# 03_POWER.net
KiCad netlist of a schematic drawn in Altium Designer
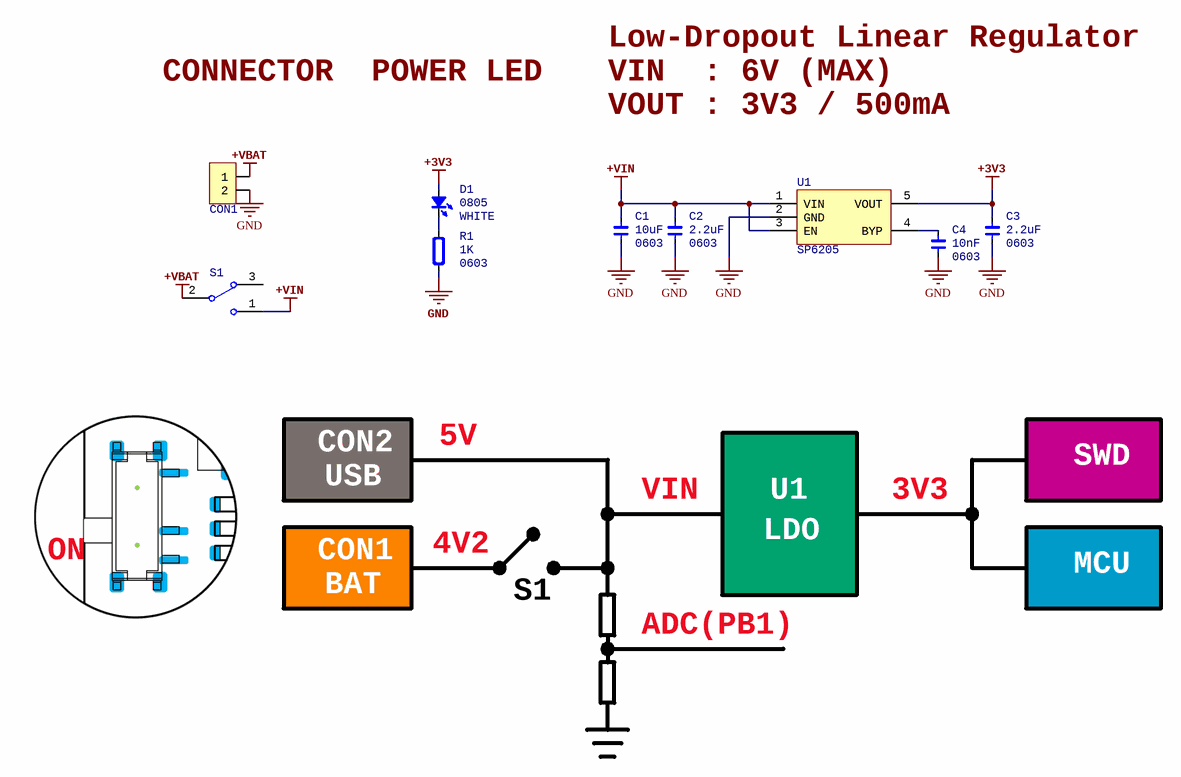
[diagram p0: [03] POWER.SchDoc]

(export (version "E")
  (design (tool "Eeschema 10.0.6"))
  (components
    (comp (ref "C1")
      (value "10uF")
      (footprint "PCB_PassiveCap:CAP_0603")
      (description "Capacitor")
      (fields (field (name "TYPE") "0603"))
      (libsource (lib "SCH_Passive") (part "Cap_0603"))
    )
    (comp (ref "C2")
      (value "2.2uF")
      (footprint "PCB_PassiveCap:CAP_0603")
      (description "Capacitor")
      (fields (field (name "TYPE") "0603"))
      (libsource (lib "SCH_Passive") (part "Cap_0603"))
    )
    (comp (ref "C3")
      (value "2.2uF")
      (footprint "PCB_PassiveCap:CAP_0603")
      (description "Capacitor")
      (fields (field (name "TYPE") "0603"))
      (libsource (lib "SCH_Passive") (part "Cap_0603"))
    )
    (comp (ref "C4")
      (value "10nF")
      (footprint "PCB_PassiveCap:CAP_0603")
      (description "Capacitor")
      (fields (field (name "TYPE") "0603"))
      (libsource (lib "SCH_Passive") (part "Cap_0603"))
    )
    (comp (ref "CON1")
      (value "MX1.25_2P")
      (footprint "PCB_Connector:MX1.25_S90_2P")
      (description "MX")
      (libsource (lib "SCH_Connector") (part "MX1.25_2P"))
    )
    (comp (ref "D1")
      (value "WHITE")
      (footprint "PCB_ActiveLED:LED_0805_YELLOW")
      (description "LED")
      (fields (field (name "TYPE") "0805"))
      (libsource (lib "SCH_Active") (part "LED_0805"))
    )
    (comp (ref "R1")
      (value "1K")
      (footprint "PCB_PassiveRes:RES_0603")
      (description "Resistor")
      (fields (field (name "TYPE") "0603"))
      (libsource (lib "SCH_Passive") (part "Res_0603"))
    )
    (comp (ref "S1")
      (value "SPDT 3P")
      (footprint "PCB_Switch:SwitchSPDT_2.8X6.6_90")
      (description "Switch")
      (libsource (lib "SCH_Switch") (part "SwitchSPDT_2.8x6.6_90"))
    )
    (comp (ref "U1")
      (value "SP6205")
      (footprint "PCB_IntegratedCircuit:SOT23-5")
      (description "Power")
      (libsource (lib "SCH_IntegratedCircuit") (part "SP6205"))
    )
  )
  (nets
    (net (code "1") (name "+3V3") (class "Default")
      (node (ref "C3") (pin "2") (pinfunction "2_2") (pintype "passive"))
      (node (ref "D1") (pin "1") (pinfunction "A_1") (pintype "passive"))
      (node (ref "U1") (pin "5") (pinfunction "VOUT_5") (pintype "passive"))
    )
    (net (code "2") (name "+VBAT") (class "Default")
      (node (ref "CON1") (pin "1") (pinfunction "1_1") (pintype "passive"))
      (node (ref "S1") (pin "2") (pinfunction "2_2") (pintype "passive"))
    )
    (net (code "3") (name "+VIN") (class "Default")
      (node (ref "C1") (pin "2") (pinfunction "2_2") (pintype "passive"))
      (node (ref "C2") (pin "2") (pinfunction "2_2") (pintype "passive"))
      (node (ref "S1") (pin "1") (pinfunction "1_1") (pintype "passive"))
      (node (ref "U1") (pin "1") (pinfunction "VIN_1") (pintype "passive"))
      (node (ref "U1") (pin "3") (pinfunction "EN_3") (pintype "power_in"))
    )
    (net (code "4") (name "GND") (class "Default")
      (node (ref "C1") (pin "1") (pinfunction "1_1") (pintype "passive"))
      (node (ref "C2") (pin "1") (pinfunction "1_1") (pintype "passive"))
      (node (ref "C3") (pin "1") (pinfunction "1_1") (pintype "passive"))
      (node (ref "C4") (pin "1") (pinfunction "1_1") (pintype "passive"))
      (node (ref "CON1") (pin "2") (pinfunction "2_2") (pintype "passive"))
      (node (ref "R1") (pin "1") (pinfunction "1_1") (pintype "passive"))
      (node (ref "U1") (pin "2") (pinfunction "GND_2") (pintype "passive"))
    )
    (net (code "5") (name "Net-(D1-K)") (class "Default")
      (node (ref "D1") (pin "2") (pinfunction "K_2") (pintype "passive"))
      (node (ref "R1") (pin "2") (pinfunction "2_2") (pintype "passive"))
    )
    (net (code "6") (name "Net-(U1-BYP)") (class "Default")
      (node (ref "C4") (pin "2") (pinfunction "2_2") (pintype "passive"))
      (node (ref "U1") (pin "4") (pinfunction "BYP_4") (pintype "passive"))
    )
    (net (code "7") (name "unconnected-(S1-Pad3)") (class "Default")
      (node (ref "S1") (pin "3") (pinfunction "3_3") (pintype "passive"))
    )
  )
)
